# openadsb_rev_a.net
KiCad netlist of a schematic drawn in Altium Designer
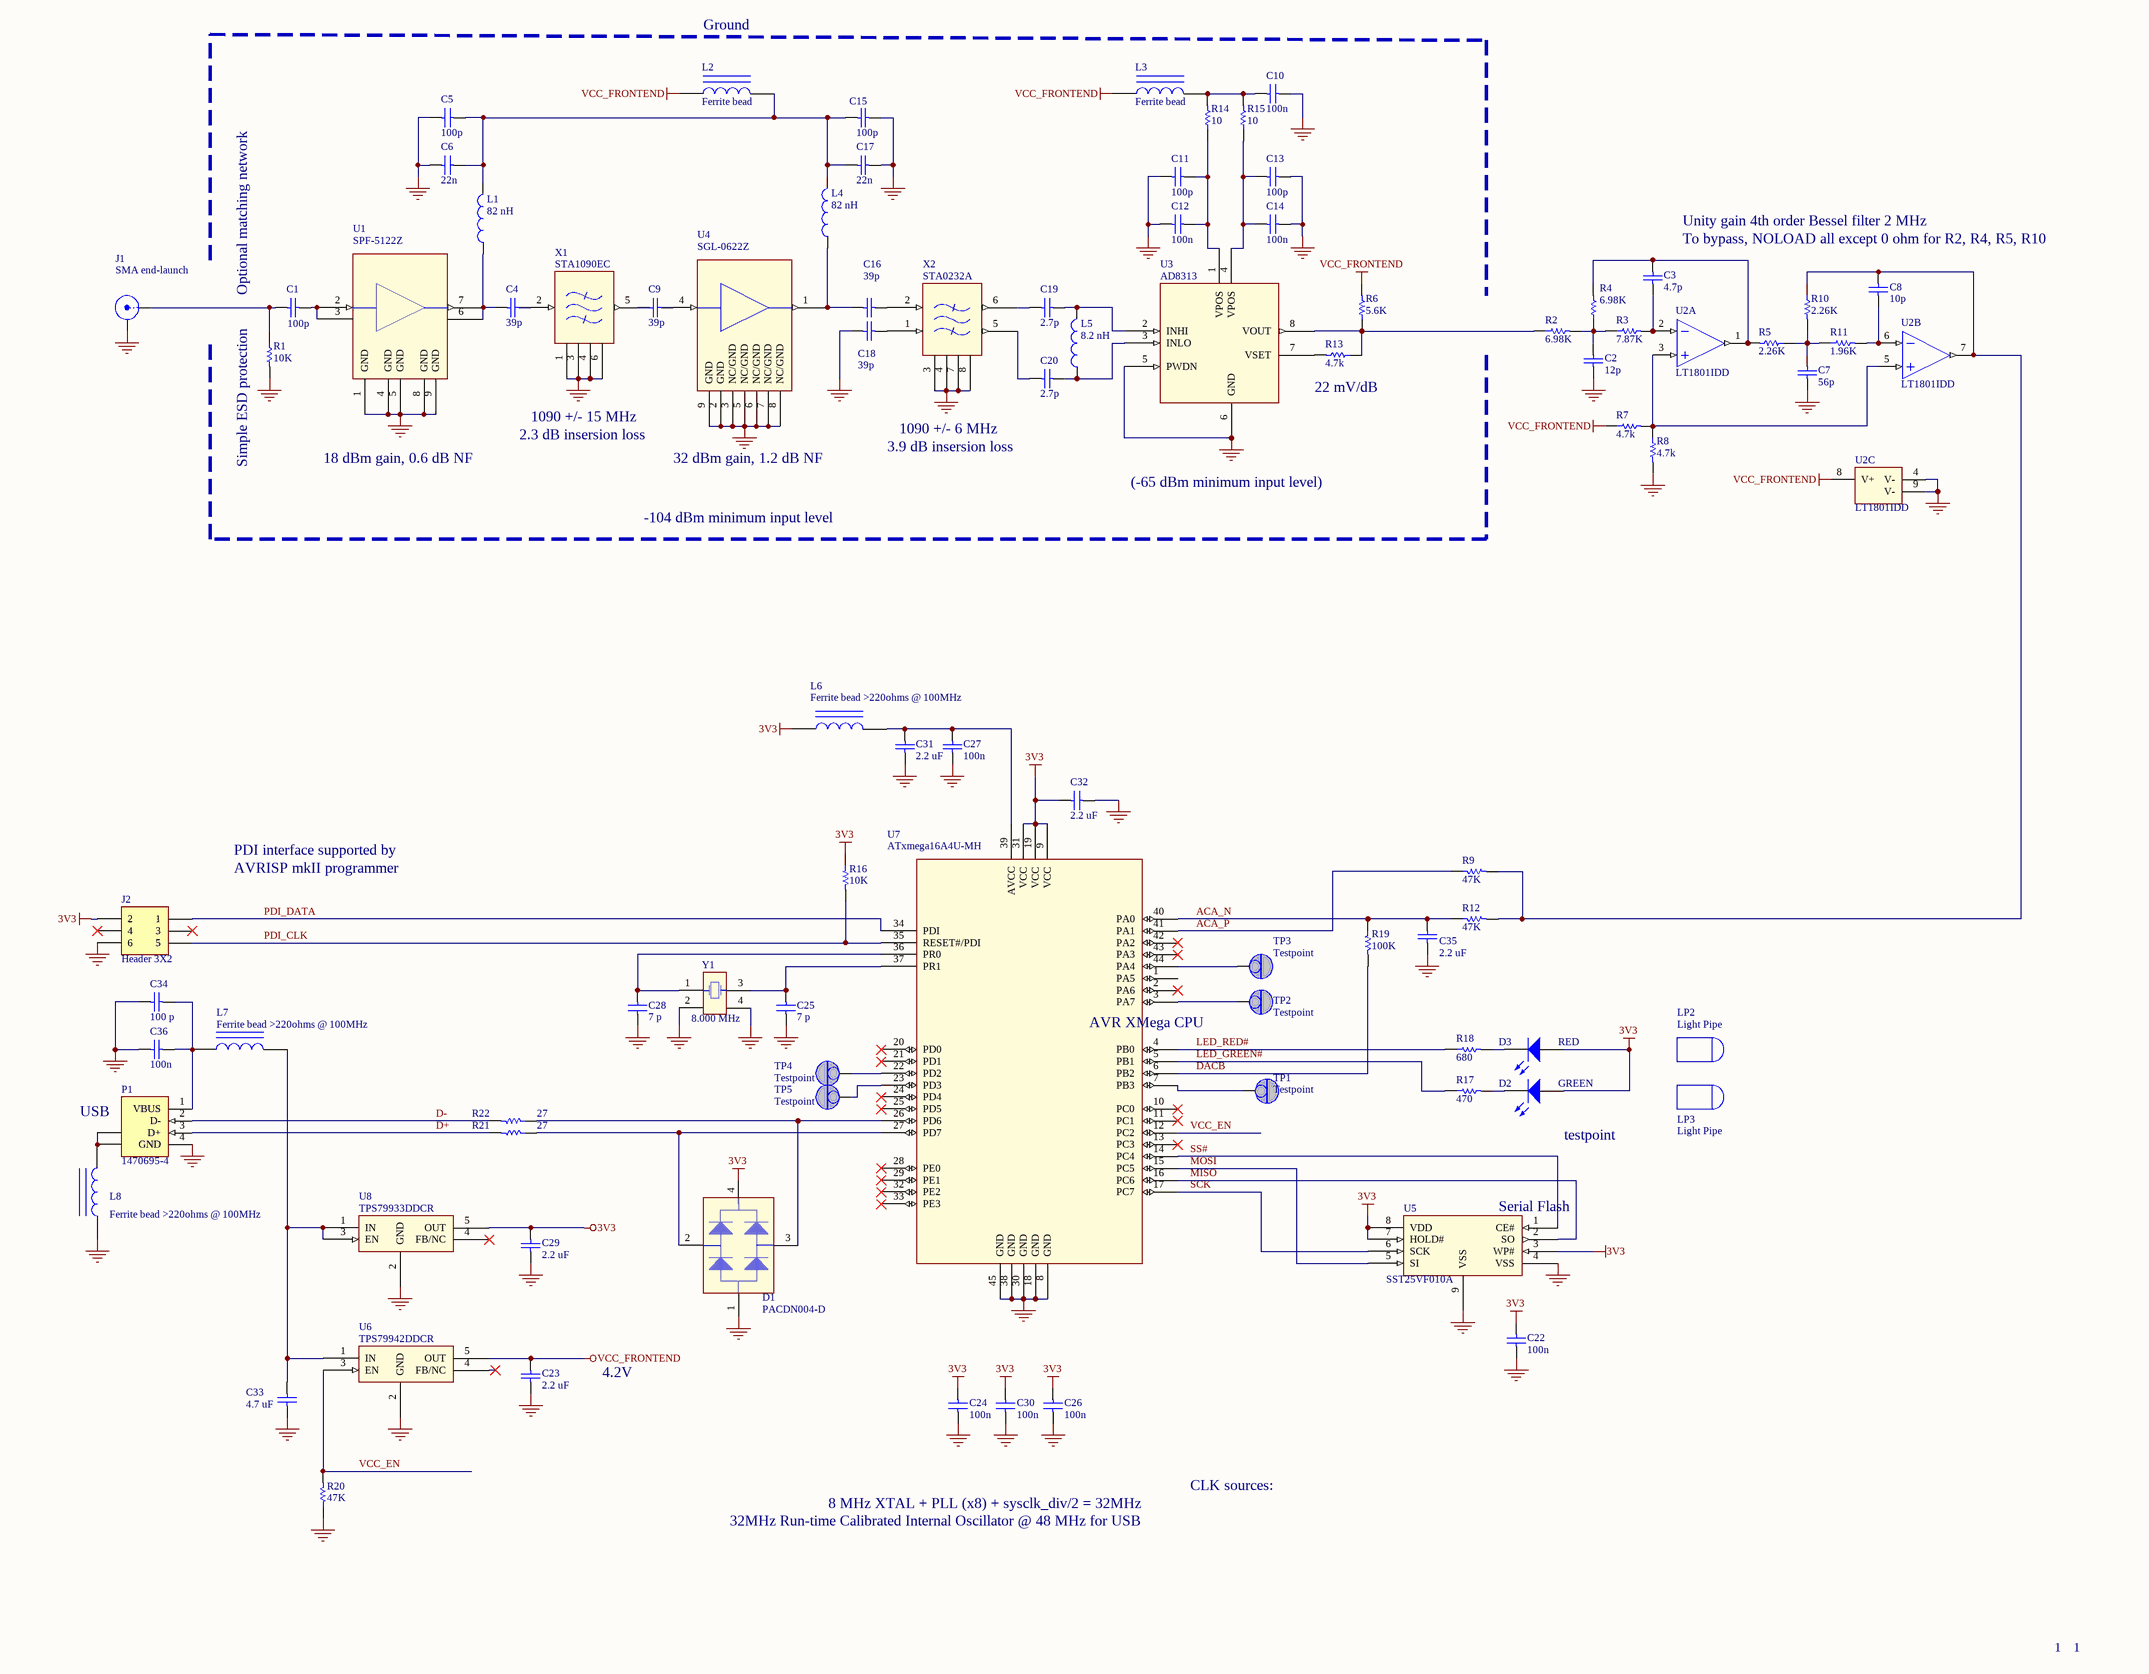
[diagram p0: openadsb_rev_a.SchDoc]

(export (version "E")
  (design (tool "Eeschema 10.0.6"))
  (components
    (comp (ref "C1")
      (value "100p")
      (description "Capacitor")
      (fields (field (name "PUBLISHER") "Altium Limited"))
      (libsource (lib "Miscellaneous Devices") (part "Cap"))
    )
    (comp (ref "C2")
      (value "12p")
      (footprint "0402")
      (description "Capacitor")
      (fields (field (name "PUBLISHER") "Altium Limited"))
      (libsource (lib "Miscellaneous Devices") (part "Cap"))
    )
    (comp (ref "C3")
      (value "4.7p")
      (footprint "0402")
      (description "Capacitor")
      (fields (field (name "PUBLISHER") "Altium Limited"))
      (libsource (lib "Miscellaneous Devices") (part "Cap"))
    )
    (comp (ref "C4")
      (value "39p")
      (description "Capacitor")
      (fields (field (name "PUBLISHER") "Altium Limited"))
      (libsource (lib "Miscellaneous Devices") (part "Cap"))
    )
    (comp (ref "C5")
      (value "100p")
      (footprint "0402")
      (description "Capacitor")
      (fields (field (name "PUBLISHER") "Altium Limited"))
      (libsource (lib "Miscellaneous Devices") (part "Cap"))
    )
    (comp (ref "C6")
      (value "22n")
      (footprint "0402")
      (description "Capacitor")
      (fields (field (name "PUBLISHER") "Altium Limited"))
      (libsource (lib "Miscellaneous Devices") (part "Cap"))
    )
    (comp (ref "C7")
      (value "56p")
      (description "Capacitor")
      (fields (field (name "PUBLISHER") "Altium Limited"))
      (libsource (lib "Miscellaneous Devices") (part "Cap"))
    )
    (comp (ref "C8")
      (value "10p")
      (footprint "0402")
      (description "Capacitor")
      (fields (field (name "PUBLISHER") "Altium Limited"))
      (libsource (lib "Miscellaneous Devices") (part "Cap"))
    )
    (comp (ref "C9")
      (value "39p")
      (description "Capacitor")
      (fields (field (name "PUBLISHER") "Altium Limited"))
      (libsource (lib "Miscellaneous Devices") (part "Cap"))
    )
    (comp (ref "C10")
      (value "100n")
      (footprint "0402")
      (description "Capacitor")
      (fields (field (name "PUBLISHER") "Altium Limited"))
      (libsource (lib "Miscellaneous Devices") (part "Cap"))
    )
    (comp (ref "C11")
      (value "100p")
      (footprint "0402")
      (description "Capacitor")
      (fields (field (name "PUBLISHER") "Altium Limited"))
      (libsource (lib "Miscellaneous Devices") (part "Cap"))
    )
    (comp (ref "C12")
      (value "100n")
      (footprint "0402")
      (description "Capacitor")
      (fields (field (name "PUBLISHER") "Altium Limited"))
      (libsource (lib "Miscellaneous Devices") (part "Cap"))
    )
    (comp (ref "C13")
      (value "100p")
      (footprint "0402")
      (description "Capacitor")
      (fields (field (name "PUBLISHER") "Altium Limited"))
      (libsource (lib "Miscellaneous Devices") (part "Cap"))
    )
    (comp (ref "C14")
      (value "100n")
      (footprint "0402")
      (description "Capacitor")
      (fields (field (name "PUBLISHER") "Altium Limited"))
      (libsource (lib "Miscellaneous Devices") (part "Cap"))
    )
    (comp (ref "C15")
      (value "100p")
      (description "Capacitor")
      (fields (field (name "PUBLISHER") "Altium Limited"))
      (libsource (lib "Miscellaneous Devices") (part "Cap"))
    )
    (comp (ref "C16")
      (value "39p")
      (description "Capacitor")
      (fields (field (name "PUBLISHER") "Altium Limited"))
      (libsource (lib "Miscellaneous Devices") (part "Cap"))
    )
    (comp (ref "C17")
      (value "22n")
      (footprint "0402")
      (description "Capacitor")
      (fields (field (name "PUBLISHER") "Altium Limited"))
      (libsource (lib "Miscellaneous Devices") (part "Cap"))
    )
    (comp (ref "C18")
      (value "39p")
      (description "Capacitor")
      (fields (field (name "PUBLISHER") "Altium Limited"))
      (libsource (lib "Miscellaneous Devices") (part "Cap"))
    )
    (comp (ref "C19")
      (value "2.7p")
      (footprint "0402")
      (description "Capacitor")
      (fields (field (name "PUBLISHER") "Altium Limited"))
      (libsource (lib "Miscellaneous Devices") (part "Cap"))
    )
    (comp (ref "C20")
      (value "2.7p")
      (footprint "0402")
      (description "Capacitor")
      (fields (field (name "PUBLISHER") "Altium Limited"))
      (libsource (lib "Miscellaneous Devices") (part "Cap"))
    )
    (comp (ref "C22")
      (value "100n")
      (footprint "0402")
      (description "Capacitor")
      (fields (field (name "PUBLISHER") "Altium Limited"))
      (libsource (lib "Miscellaneous Devices") (part "Cap"))
    )
    (comp (ref "C23")
      (value "2.2 uF")
      (footprint "1608[0603]")
      (description "Capacitor")
      (fields (field (name "PUBLISHER") "Altium Limited"))
      (libsource (lib "Miscellaneous Devices") (part "Cap"))
    )
    (comp (ref "C24")
      (value "100n")
      (footprint "0402")
      (description "Capacitor")
      (fields (field (name "PUBLISHER") "Altium Limited"))
      (libsource (lib "Miscellaneous Devices") (part "Cap"))
    )
    (comp (ref "C25")
      (value "7 p")
      (description "Capacitor")
      (fields (field (name "PUBLISHER") "Altium Limited"))
      (libsource (lib "Miscellaneous Devices") (part "Cap"))
    )
    (comp (ref "C26")
      (value "100n")
      (footprint "0402")
      (description "Capacitor")
      (fields (field (name "PUBLISHER") "Altium Limited"))
      (libsource (lib "Miscellaneous Devices") (part "Cap"))
    )
    (comp (ref "C27")
      (value "100n")
      (footprint "0402")
      (description "Capacitor")
      (fields (field (name "PUBLISHER") "Altium Limited"))
      (libsource (lib "Miscellaneous Devices") (part "Cap"))
    )
    (comp (ref "C28")
      (value "7 p")
      (description "Capacitor")
      (fields (field (name "PUBLISHER") "Altium Limited"))
      (libsource (lib "Miscellaneous Devices") (part "Cap"))
    )
    (comp (ref "C29")
      (value "2.2 uF")
      (footprint "1608[0603]")
      (description "Capacitor")
      (fields (field (name "PUBLISHER") "Altium Limited"))
      (libsource (lib "Miscellaneous Devices") (part "Cap"))
    )
    (comp (ref "C30")
      (value "100n")
      (footprint "0402")
      (description "Capacitor")
      (fields (field (name "PUBLISHER") "Altium Limited"))
      (libsource (lib "Miscellaneous Devices") (part "Cap"))
    )
    (comp (ref "C31")
      (value "2.2 uF")
      (description "Capacitor")
      (fields (field (name "PUBLISHER") "Altium Limited"))
      (libsource (lib "Miscellaneous Devices") (part "Cap"))
    )
    (comp (ref "C32")
      (value "2.2 uF")
      (footprint "1608[0603]")
      (description "Capacitor")
      (fields (field (name "PUBLISHER") "Altium Limited"))
      (libsource (lib "Miscellaneous Devices") (part "Cap"))
    )
    (comp (ref "C33")
      (value "4.7 uF")
      (description "Capacitor")
      (fields (field (name "PUBLISHER") "Altium Limited"))
      (libsource (lib "Miscellaneous Devices") (part "Cap"))
    )
    (comp (ref "C34")
      (value "100 p")
      (footprint "0402")
      (description "Capacitor")
      (fields (field (name "PUBLISHER") "Altium Limited"))
      (libsource (lib "Miscellaneous Devices") (part "Cap"))
    )
    (comp (ref "C35")
      (value "2.2 uF")
      (description "Capacitor")
      (fields (field (name "PUBLISHER") "Altium Limited"))
      (libsource (lib "Miscellaneous Devices") (part "Cap"))
    )
    (comp (ref "C36")
      (value "100n")
      (footprint "0402")
      (description "Capacitor")
      (fields (field (name "PUBLISHER") "Altium Limited"))
      (libsource (lib "Miscellaneous Devices") (part "Cap"))
    )
    (comp (ref "D1")
      (value "PACDN004-D")
      (footprint "SOT-143-RC4_L")
      (description "ESD protection")
      (fields (field (name "MANUFACTURER") "On Semi"))
      (libsource (lib "Schlib1") (part "PACDN004"))
    )
    (comp (ref "D2")
      (value "GREEN")
      (footprint "LED0603")
      (description "Typical BLUE SiC LED")
      (fields (field (name "PUBLISHER") "Altium Limited"))
      (libsource (lib "Miscellaneous Devices") (part "LED3"))
    )
    (comp (ref "D3")
      (value "RED")
      (footprint "LED0603")
      (description "Typical BLUE SiC LED")
      (fields (field (name "PUBLISHER") "Altium Limited"))
      (libsource (lib "Miscellaneous Devices") (part "LED3"))
    )
    (comp (ref "J1")
      (value "SMA end-launch")
      (footprint "SMA_ENDLAUNCH")
      (description "SMB Straight Connector")
      (fields (field (name "PUBLISHER") "Altium Limited"))
      (libsource (lib "Miscellaneous Connectors") (part "SMB"))
    )
    (comp (ref "J2")
      (value "Header 3X2")
      (footprint "HDR2X3")
      (description "Header, 3-Pin, Dual row")
      (fields (field (name "PUBLISHER") "Altium Limited"))
      (libsource (lib "Miscellaneous Connectors") (part "Header 3X2"))
    )
    (comp (ref "L1")
      (value "82 nH")
      (footprint "0402")
      (description "Inductor")
      (fields
        (field (name "PARTNUMBER") "TKS2388CT")
        (field (name "MANUFACTURER") "TOKO")
        (field (name "PUBLISHER") "Altium Limited")
      )
      (libsource (lib "Miscellaneous Devices") (part "Inductor"))
    )
    (comp (ref "L2")
      (value "Ferrite bead")
      (footprint "0402")
      (description "Magnetic-Core Inductor")
      (fields (field (name "PUBLISHER") "Altium Limited"))
      (libsource (lib "") (part "Inductor Iron_1"))
    )
    (comp (ref "L3")
      (value "Ferrite bead")
      (footprint "0402")
      (description "Magnetic-Core Inductor")
      (fields (field (name "PUBLISHER") "Altium Limited"))
      (libsource (lib "") (part "Inductor Iron_1"))
    )
    (comp (ref "L4")
      (value "82 nH")
      (footprint "0402")
      (description "Inductor")
      (fields (field (name "PUBLISHER") "Altium Limited"))
      (libsource (lib "Miscellaneous Devices") (part "Inductor"))
    )
    (comp (ref "L5")
      (value "8.2 nH")
      (footprint "0402")
      (description "Inductor")
      (fields (field (name "PUBLISHER") "Altium Limited"))
      (libsource (lib "Miscellaneous Devices") (part "Inductor"))
    )
    (comp (ref "L6")
      (value "Ferrite bead >220ohms @ 100MHz")
      (footprint "0402")
      (description "Magnetic-Core Inductor")
      (fields (field (name "PUBLISHER") "Altium Limited"))
      (libsource (lib "Miscellaneous Devices") (part "Inductor Iron"))
    )
    (comp (ref "L7")
      (value "Ferrite bead >220ohms @ 100MHz")
      (footprint "0402")
      (description "Magnetic-Core Inductor")
      (fields (field (name "PUBLISHER") "Altium Limited"))
      (libsource (lib "Miscellaneous Devices") (part "Inductor Iron"))
    )
    (comp (ref "L8")
      (value "Ferrite bead >220ohms @ 100MHz")
      (footprint "0402")
      (description "Magnetic-Core Inductor")
      (fields (field (name "PUBLISHER") "Altium Limited"))
      (libsource (lib "Miscellaneous Devices") (part "Inductor Iron"))
    )
    (comp (ref "LP2")
      (value "Light Pipe")
      (footprint "LIGHTPIPE")
      (description "light pipe")
      (fields (field (name "PARTNUMBER") "PLP2-215") (field (name "MANUFACTURER") "Bivar"))
      (libsource (lib "Schlib1") (part "LIGHT_PIPE"))
    )
    (comp (ref "LP3")
      (value "Light Pipe")
      (description "light pipe")
      (fields (field (name "PARTNUMBER") "PLP2-215") (field (name "MANUFACTURER") "Bivar"))
      (libsource (lib "Schlib1") (part "LIGHT_PIPE"))
    )
    (comp (ref "P1")
      (value "1470695-4")
      (footprint "1470695A")
      (description "USB 1.1, Right Angle, SMT, A Type, Plug, 4 Position, Black")
      (fields (field (name "PUBLISHER") "Altium Limited"))
      (libsource (lib "AMP Serial Bus USB") (part "1470695-4"))
    )
    (comp (ref "R1")
      (value "10K")
      (footprint "0402")
      (description "Resistor")
      (fields (field (name "PUBLISHER") "Altium Limited"))
      (libsource (lib "Miscellaneous Devices") (part "Res1"))
    )
    (comp (ref "R2")
      (value "6.98K")
      (footprint "0402")
      (description "Resistor")
      (fields (field (name "PUBLISHER") "Altium Limited"))
      (libsource (lib "Miscellaneous Devices") (part "Res1"))
    )
    (comp (ref "R3")
      (value "7.87K")
      (footprint "0402")
      (description "Resistor")
      (fields (field (name "PUBLISHER") "Altium Limited"))
      (libsource (lib "Miscellaneous Devices") (part "Res1"))
    )
    (comp (ref "R4")
      (value "6.98K")
      (footprint "0402")
      (description "Resistor")
      (fields (field (name "PUBLISHER") "Altium Limited"))
      (libsource (lib "Miscellaneous Devices") (part "Res1"))
    )
    (comp (ref "R5")
      (value "2.26K")
      (footprint "0402")
      (description "Resistor")
      (fields (field (name "PUBLISHER") "Altium Limited"))
      (libsource (lib "Miscellaneous Devices") (part "Res1"))
    )
    (comp (ref "R6")
      (value "5.6K")
      (footprint "0402")
      (description "Resistor")
      (fields (field (name "PUBLISHER") "Altium Limited"))
      (libsource (lib "Miscellaneous Devices") (part "Res1"))
    )
    (comp (ref "R7")
      (value "4.7k")
      (footprint "0402")
      (description "Resistor")
      (fields (field (name "PUBLISHER") "Altium Limited"))
      (libsource (lib "Miscellaneous Devices") (part "Res1"))
    )
    (comp (ref "R8")
      (value "4.7k")
      (footprint "0402")
      (description "Resistor")
      (fields (field (name "PUBLISHER") "Altium Limited"))
      (libsource (lib "Miscellaneous Devices") (part "Res1"))
    )
    (comp (ref "R9")
      (value "47K")
      (footprint "0402")
      (description "Resistor")
      (fields (field (name "PUBLISHER") "Altium Limited"))
      (libsource (lib "Miscellaneous Devices") (part "Res1"))
    )
    (comp (ref "R10")
      (value "2.26K")
      (footprint "0402")
      (description "Resistor")
      (fields (field (name "PUBLISHER") "Altium Limited"))
      (libsource (lib "Miscellaneous Devices") (part "Res1"))
    )
    (comp (ref "R11")
      (value "1.96K")
      (footprint "0402")
      (description "Resistor")
      (fields (field (name "PUBLISHER") "Altium Limited"))
      (libsource (lib "Miscellaneous Devices") (part "Res1"))
    )
    (comp (ref "R12")
      (value "47K")
      (footprint "0402")
      (description "Resistor")
      (fields (field (name "PUBLISHER") "Altium Limited"))
      (libsource (lib "Miscellaneous Devices") (part "Res1"))
    )
    (comp (ref "R13")
      (value "4.7k")
      (footprint "0402")
      (description "Resistor")
      (fields (field (name "PUBLISHER") "Altium Limited"))
      (libsource (lib "Miscellaneous Devices") (part "Res1"))
    )
    (comp (ref "R14")
      (value "10")
      (footprint "0402")
      (description "Resistor")
      (fields (field (name "PUBLISHER") "Altium Limited"))
      (libsource (lib "Miscellaneous Devices") (part "Res1"))
    )
    (comp (ref "R15")
      (value "10")
      (footprint "0402")
      (description "Resistor")
      (fields (field (name "PUBLISHER") "Altium Limited"))
      (libsource (lib "Miscellaneous Devices") (part "Res1"))
    )
    (comp (ref "R16")
      (value "10K")
      (footprint "0402")
      (description "Resistor")
      (fields (field (name "PUBLISHER") "Altium Limited"))
      (libsource (lib "Miscellaneous Devices") (part "Res1"))
    )
    (comp (ref "R17")
      (value "470")
      (footprint "0402")
      (description "Resistor")
      (fields (field (name "PUBLISHER") "Altium Limited"))
      (libsource (lib "Miscellaneous Devices") (part "Res1"))
    )
    (comp (ref "R18")
      (value "680")
      (footprint "0402")
      (description "Resistor")
      (fields (field (name "PUBLISHER") "Altium Limited"))
      (libsource (lib "Miscellaneous Devices") (part "Res1"))
    )
    (comp (ref "R19")
      (value "100K")
      (footprint "0402")
      (description "Resistor")
      (fields (field (name "PUBLISHER") "Altium Limited"))
      (libsource (lib "Miscellaneous Devices") (part "Res1"))
    )
    (comp (ref "R20")
      (value "47K")
      (footprint "0402")
      (description "Resistor")
      (fields (field (name "PUBLISHER") "Altium Limited"))
      (libsource (lib "Miscellaneous Devices") (part "Res1"))
    )
    (comp (ref "R21")
      (value "27")
      (footprint "0402")
      (description "Resistor")
      (fields (field (name "PUBLISHER") "Altium Limited"))
      (libsource (lib "Miscellaneous Devices") (part "Res1"))
    )
    (comp (ref "R22")
      (value "27")
      (footprint "0402")
      (description "Resistor")
      (fields (field (name "PUBLISHER") "Altium Limited"))
      (libsource (lib "Miscellaneous Devices") (part "Res1"))
    )
    (comp (ref "TP1")
      (value "Testpoint")
      (footprint "Testpoint_via")
      (libsource (lib "") (part "Testpoint_1"))
    )
    (comp (ref "TP2")
      (value "Testpoint")
      (footprint "Testpoint_via")
      (libsource (lib "") (part "Testpoint_1"))
    )
    (comp (ref "TP3")
      (value "Testpoint")
      (footprint "Testpoint_via")
      (libsource (lib "") (part "Testpoint_1"))
    )
    (comp (ref "TP4")
      (value "Testpoint")
      (footprint "Testpoint_via")
      (libsource (lib "adsb_usb") (part "Testpoint"))
    )
    (comp (ref "TP5")
      (value "Testpoint")
      (footprint "Testpoint_via")
      (libsource (lib "adsb_usb") (part "Testpoint"))
    )
    (comp (ref "U1")
      (value "SPF-5122Z")
      (footprint "DFN8_2x2mm")
      (fields (field (name "MANUFACTURER") "Sirenza"))
      (libsource (lib "Schlib1") (part "LNA1"))
    )
    (comp (ref "U2")
      (value "LT1801IDD")
      (footprint "DFN8_3x3mm")
      (fields (field (name "MANUFACTURER") "Linear Tech"))
      (libsource (lib "") (part "LT1801_1"))
    )
    (comp (ref "U3")
      (value "AD8313")
      (footprint "MSOP-MS8_N")
      (description "AD8313 Logarithmic Amp")
      (libsource (lib "Schlib1") (part "AD8313"))
    )
    (comp (ref "U4")
      (value "SGL-0622Z")
      (footprint "DFN8_2x2mm")
      (fields (field (name "MANUFACTURER") "RFMD"))
      (libsource (lib "adsb_usb") (part "SGL0622Z"))
    )
    (comp (ref "U5")
      (value "SST25VF010A")
      (footprint "WSON-8")
      (fields (field (name "MANUFACTURER") "SST"))
      (libsource (lib "Schlib1") (part "SERFLASH"))
    )
    (comp (ref "U6")
      (value "TPS79942DDCR")
      (footprint "SOT23-5AN")
      (fields (field (name "MANUFACTURER") "Texas Instruments"))
      (libsource (lib "Schlib1") (part "TPS799XX"))
    )
    (comp (ref "U7")
      (value "ATxmega16A4U-MH")
      (footprint "QFN50P700X700-44W3N")
      (fields (field (name "MANUFACTURER") "Atmel"))
      (libsource (lib "adsb_usb") (part "ATXMEGA164AU"))
    )
    (comp (ref "U8")
      (value "TPS79933DDCR")
      (footprint "SOT23-5AN")
      (fields (field (name "MANUFACTURER") "Texas Instruments"))
      (libsource (lib "Schlib1") (part "TPS799XX"))
    )
    (comp (ref "X1")
      (value "STA1090EC")
      (footprint "STA1090EC")
      (libsource (lib "Schlib1") (part "BP_FILTER_UNBAL"))
    )
    (comp (ref "X2") (value "STA0232A") (libsource (lib "Schlib1") (part "BP_FILTER_BAL2")))
    (comp (ref "Y1")
      (value "8.000 MHz")
      (footprint "ABM3C")
      (fields (field (name "MANUFACTURER") "Abracon") (field (name "PARTNUMBER") "ABM3B-8.000MHZ-B2-T"))
      (libsource (lib "Schlib1") (part "XTAL_4"))
    )
  )
  (nets
    (net (code "1") (name "/ACA_N") (class "Default")
      (node (ref "C35") (pin "1") (pinfunction "1_1") (pintype "passive"))
      (node (ref "R12") (pin "1") (pinfunction "1_1") (pintype "passive"))
      (node (ref "R19") (pin "1") (pinfunction "1_1") (pintype "passive"))
      (node (ref "U7") (pin "40") (pinfunction "PA0_40") (pintype "bidirectional"))
    )
    (net (code "2") (name "/ACA_P") (class "Default")
      (node (ref "R9") (pin "1") (pinfunction "1_1") (pintype "passive"))
      (node (ref "U7") (pin "41") (pinfunction "PA1_41") (pintype "bidirectional"))
    )
    (net (code "3") (name "/D+") (class "Default")
      (node (ref "P1") (pin "3") (pinfunction "D+_3") (pintype "input"))
      (node (ref "R21") (pin "2") (pinfunction "2_2") (pintype "passive"))
    )
    (net (code "4") (name "/D-") (class "Default")
      (node (ref "P1") (pin "2") (pinfunction "D-_2") (pintype "input"))
      (node (ref "R22") (pin "2") (pinfunction "2_2") (pintype "passive"))
    )
    (net (code "5") (name "/DACB") (class "Default")
      (node (ref "R19") (pin "2") (pinfunction "2_2") (pintype "passive"))
      (node (ref "U7") (pin "6") (pinfunction "PB2_6") (pintype "bidirectional"))
    )
    (net (code "6") (name "/LED_GREEN#") (class "Default")
      (node (ref "R17") (pin "1") (pinfunction "1_1") (pintype "passive"))
      (node (ref "U7") (pin "5") (pinfunction "PB1_5") (pintype "bidirectional"))
    )
    (net (code "7") (name "/LED_RED#") (class "Default")
      (node (ref "R18") (pin "1") (pinfunction "1_1") (pintype "passive"))
      (node (ref "U7") (pin "4") (pinfunction "PB0_4") (pintype "bidirectional"))
    )
    (net (code "8") (name "/MISO") (class "Default")
      (node (ref "U5") (pin "2") (pinfunction "SO_2") (pintype "output"))
      (node (ref "U7") (pin "16") (pinfunction "PC6_16") (pintype "bidirectional"))
    )
    (net (code "9") (name "/MOSI") (class "Default")
      (node (ref "U5") (pin "5") (pinfunction "SI_5") (pintype "input"))
      (node (ref "U7") (pin "15") (pinfunction "PC5_15") (pintype "bidirectional"))
    )
    (net (code "10") (name "/PDI_CLK") (class "Default")
      (node (ref "J2") (pin "5") (pinfunction "5_5") (pintype "passive"))
      (node (ref "R16") (pin "2") (pinfunction "2_2") (pintype "passive"))
      (node (ref "U7") (pin "35") (pinfunction "RESET#/PDI_35") (pintype "passive"))
    )
    (net (code "11") (name "/PDI_DATA") (class "Default")
      (node (ref "J2") (pin "1") (pinfunction "1_1") (pintype "passive"))
      (node (ref "U7") (pin "34") (pinfunction "PDI_34") (pintype "passive"))
    )
    (net (code "12") (name "/SCK") (class "Default")
      (node (ref "U5") (pin "6") (pinfunction "SCK_6") (pintype "input"))
      (node (ref "U7") (pin "17") (pinfunction "PC7_17") (pintype "bidirectional"))
    )
    (net (code "13") (name "/SS#") (class "Default")
      (node (ref "U5") (pin "1") (pinfunction "CE#_1") (pintype "input"))
      (node (ref "U7") (pin "14") (pinfunction "PC4_14") (pintype "bidirectional"))
    )
    (net (code "14") (name "/VCC_EN") (class "Default")
      (node (ref "R20") (pin "2") (pinfunction "2_2") (pintype "passive"))
      (node (ref "U6") (pin "3") (pinfunction "EN_3") (pintype "input"))
      (node (ref "U7") (pin "12") (pinfunction "PC2_12") (pintype "bidirectional"))
    )
    (net (code "15") (name "3V3") (class "Default")
      (node (ref "C22") (pin "1") (pinfunction "1_1") (pintype "passive"))
      (node (ref "C24") (pin "1") (pinfunction "1_1") (pintype "passive"))
      (node (ref "C26") (pin "1") (pinfunction "1_1") (pintype "passive"))
      (node (ref "C29") (pin "1") (pinfunction "1_1") (pintype "passive"))
      (node (ref "C30") (pin "1") (pinfunction "1_1") (pintype "passive"))
      (node (ref "C32") (pin "1") (pinfunction "1_1") (pintype "passive"))
      (node (ref "D1") (pin "4") (pinfunction "V_4") (pintype "passive"))
      (node (ref "D2") (pin "A") (pinfunction "A_A") (pintype "passive"))
      (node (ref "D3") (pin "A") (pinfunction "A_A") (pintype "passive"))
      (node (ref "J2") (pin "2") (pinfunction "2_2") (pintype "passive"))
      (node (ref "L6") (pin "2") (pinfunction "2_2") (pintype "passive"))
      (node (ref "R16") (pin "1") (pinfunction "1_1") (pintype "passive"))
      (node (ref "U5") (pin "3") (pinfunction "WP#_3") (pintype "input"))
      (node (ref "U5") (pin "7") (pinfunction "HOLD#_7") (pintype "input"))
      (node (ref "U5") (pin "8") (pinfunction "VDD_8") (pintype "power_in"))
      (node (ref "U7") (pin "19") (pinfunction "VCC_19") (pintype "power_in"))
      (node (ref "U7") (pin "31") (pinfunction "VCC_31") (pintype "power_in"))
      (node (ref "U7") (pin "9") (pinfunction "VCC_9") (pintype "power_in"))
      (node (ref "U8") (pin "5") (pinfunction "OUT_5") (pintype "power_in"))
    )
    (net (code "16") (name "GND") (class "Default")
      (node (ref "C10") (pin "2") (pinfunction "2_2") (pintype "passive"))
      (node (ref "C11") (pin "2") (pinfunction "2_2") (pintype "passive"))
      (node (ref "C12") (pin "2") (pinfunction "2_2") (pintype "passive"))
      (node (ref "C13") (pin "1") (pinfunction "1_1") (pintype "passive"))
      (node (ref "C14") (pin "1") (pinfunction "1_1") (pintype "passive"))
      (node (ref "C15") (pin "2") (pinfunction "2_2") (pintype "passive"))
      (node (ref "C17") (pin "2") (pinfunction "2_2") (pintype "passive"))
      (node (ref "C18") (pin "1") (pinfunction "1_1") (pintype "passive"))
      (node (ref "C2") (pin "1") (pinfunction "1_1") (pintype "passive"))
      (node (ref "C22") (pin "2") (pinfunction "2_2") (pintype "passive"))
      (node (ref "C23") (pin "2") (pinfunction "2_2") (pintype "passive"))
      (node (ref "C24") (pin "2") (pinfunction "2_2") (pintype "passive"))
      (node (ref "C25") (pin "1") (pinfunction "1_1") (pintype "passive"))
      (node (ref "C26") (pin "2") (pinfunction "2_2") (pintype "passive"))
      (node (ref "C27") (pin "2") (pinfunction "2_2") (pintype "passive"))
      (node (ref "C28") (pin "1") (pinfunction "1_1") (pintype "passive"))
      (node (ref "C29") (pin "2") (pinfunction "2_2") (pintype "passive"))
      (node (ref "C30") (pin "2") (pinfunction "2_2") (pintype "passive"))
      (node (ref "C31") (pin "2") (pinfunction "2_2") (pintype "passive"))
      (node (ref "C32") (pin "2") (pinfunction "2_2") (pintype "passive"))
      (node (ref "C33") (pin "2") (pinfunction "2_2") (pintype "passive"))
      (node (ref "C34") (pin "2") (pinfunction "2_2") (pintype "passive"))
      (node (ref "C35") (pin "2") (pinfunction "2_2") (pintype "passive"))
      (node (ref "C36") (pin "2") (pinfunction "2_2") (pintype "passive"))
      (node (ref "C5") (pin "2") (pinfunction "2_2") (pintype "passive"))
      (node (ref "C6") (pin "2") (pinfunction "2_2") (pintype "passive"))
      (node (ref "C7") (pin "1") (pinfunction "1_1") (pintype "passive"))
      (node (ref "D1") (pin "1") (pinfunction "GND_1") (pintype "passive"))
      (node (ref "J1") (pin "2") (pinfunction "Y_2") (pintype "passive"))
      (node (ref "J2") (pin "6") (pinfunction "6_6") (pintype "passive"))
      (node (ref "L8") (pin "2") (pinfunction "2_2") (pintype "passive"))
      (node (ref "P1") (pin "4") (pinfunction "GND_4") (pintype "power_in"))
      (node (ref "R1") (pin "2") (pinfunction "2_2") (pintype "passive"))
      (node (ref "R20") (pin "1") (pinfunction "1_1") (pintype "passive"))
      (node (ref "R8") (pin "2") (pinfunction "2_2") (pintype "passive"))
      (node (ref "U1") (pin "1") (pinfunction "GND_1") (pintype "power_in"))
      (node (ref "U1") (pin "4") (pinfunction "GND_4") (pintype "power_in"))
      (node (ref "U1") (pin "5") (pinfunction "GND_5") (pintype "power_in"))
      (node (ref "U1") (pin "8") (pinfunction "GND_8") (pintype "power_in"))
      (node (ref "U1") (pin "9") (pinfunction "GND_9") (pintype "power_in"))
      (node (ref "U2") (pin "4") (pinfunction "V-_4") (pintype "power_in"))
      (node (ref "U2") (pin "9") (pinfunction "V-_9") (pintype "power_in"))
      (node (ref "U3") (pin "5") (pinfunction "PWDN_5") (pintype "input"))
      (node (ref "U3") (pin "6") (pinfunction "GND_6") (pintype "power_in"))
      (node (ref "U4") (pin "2") (pinfunction "GND_2") (pintype "passive"))
      (node (ref "U4") (pin "3") (pinfunction "NC/GND_3") (pintype "passive"))
      (node (ref "U4") (pin "5") (pinfunction "NC/GND_5") (pintype "passive"))
      (node (ref "U4") (pin "6") (pinfunction "NC/GND_6") (pintype "passive"))
      (node (ref "U4") (pin "7") (pinfunction "NC/GND_7") (pintype "passive"))
      (node (ref "U4") (pin "8") (pinfunction "NC/GND_8") (pintype "passive"))
      (node (ref "U4") (pin "9") (pinfunction "GND_9") (pintype "power_in"))
      (node (ref "U5") (pin "4") (pinfunction "VSS_4") (pintype "power_in"))
      (node (ref "U5") (pin "9") (pinfunction "VSS_9") (pintype "power_in"))
      (node (ref "U6") (pin "2") (pinfunction "GND_2") (pintype "power_in"))
      (node (ref "U7") (pin "18") (pinfunction "GND_18") (pintype "power_in"))
      (node (ref "U7") (pin "30") (pinfunction "GND_30") (pintype "power_in"))
      (node (ref "U7") (pin "38") (pinfunction "GND_38") (pintype "power_in"))
      (node (ref "U7") (pin "45") (pinfunction "GND_45") (pintype "power_in"))
      (node (ref "U7") (pin "8") (pinfunction "GND_8") (pintype "power_in"))
      (node (ref "U8") (pin "2") (pinfunction "GND_2") (pintype "power_in"))
      (node (ref "X1") (pin "1") (pinfunction "GND_1") (pintype "passive"))
      (node (ref "X1") (pin "3") (pinfunction "GND_3") (pintype "passive"))
      (node (ref "X1") (pin "4") (pinfunction "GND_4") (pintype "passive"))
      (node (ref "X1") (pin "6") (pinfunction "GND_6") (pintype "passive"))
      (node (ref "X2") (pin "3") (pinfunction "GND_3") (pintype "passive"))
      (node (ref "X2") (pin "4") (pinfunction "GND_4") (pintype "passive"))
      (node (ref "X2") (pin "7") (pinfunction "GND_7") (pintype "passive"))
      (node (ref "X2") (pin "8") (pinfunction "GND_8") (pintype "passive"))
      (node (ref "Y1") (pin "2") (pinfunction "GND_2") (pintype "passive"))
      (node (ref "Y1") (pin "4") (pinfunction "OSC1_4") (pintype "passive"))
    )
    (net (code "17") (name "Net-(C2-Pad2)") (class "Default")
      (node (ref "C2") (pin "2") (pinfunction "2_2") (pintype "passive"))
      (node (ref "R2") (pin "2") (pinfunction "2_2") (pintype "passive"))
      (node (ref "R3") (pin "1") (pinfunction "1_1") (pintype "passive"))
      (node (ref "R4") (pin "1") (pinfunction "1_1") (pintype "passive"))
    )
    (net (code "18") (name "Net-(C7-Pad2)") (class "Default")
      (node (ref "C7") (pin "2") (pinfunction "2_2") (pintype "passive"))
      (node (ref "R10") (pin "2") (pinfunction "2_2") (pintype "passive"))
      (node (ref "R11") (pin "1") (pinfunction "1_1") (pintype "passive"))
      (node (ref "R5") (pin "1") (pinfunction "1_1") (pintype "passive"))
    )
    (net (code "19") (name "Net-(C10-Pad1)") (class "Default")
      (node (ref "C10") (pin "1") (pinfunction "1_1") (pintype "passive"))
      (node (ref "L3") (pin "2") (pinfunction "2_2") (pintype "passive"))
      (node (ref "R14") (pin "2") (pinfunction "2_2") (pintype "passive"))
      (node (ref "R15") (pin "2") (pinfunction "2_2") (pintype "passive"))
    )
    (net (code "20") (name "Net-(C11-Pad1)") (class "Default")
      (node (ref "C11") (pin "1") (pinfunction "1_1") (pintype "passive"))
      (node (ref "C12") (pin "1") (pinfunction "1_1") (pintype "passive"))
      (node (ref "R14") (pin "1") (pinfunction "1_1") (pintype "passive"))
      (node (ref "U3") (pin "1") (pinfunction "VPOS_1") (pintype "power_in"))
    )
    (net (code "21") (name "Net-(C13-Pad2)") (class "Default")
      (node (ref "C13") (pin "2") (pinfunction "2_2") (pintype "passive"))
      (node (ref "C14") (pin "2") (pinfunction "2_2") (pintype "passive"))
      (node (ref "R15") (pin "1") (pinfunction "1_1") (pintype "passive"))
      (node (ref "U3") (pin "4") (pinfunction "VPOS_4") (pintype "power_in"))
    )
    (net (code "22") (name "Net-(C15-Pad1)") (class "Default")
      (node (ref "C15") (pin "1") (pinfunction "1_1") (pintype "passive"))
      (node (ref "C17") (pin "1") (pinfunction "1_1") (pintype "passive"))
      (node (ref "C5") (pin "1") (pinfunction "1_1") (pintype "passive"))
      (node (ref "C6") (pin "1") (pinfunction "1_1") (pintype "passive"))
      (node (ref "L1") (pin "2") (pinfunction "2_2") (pintype "passive"))
      (node (ref "L2") (pin "2") (pinfunction "2_2") (pintype "passive"))
      (node (ref "L4") (pin "2") (pinfunction "2_2") (pintype "passive"))
    )
    (net (code "23") (name "Net-(D2-PadK)") (class "Default")
      (node (ref "D2") (pin "K") (pinfunction "K_K") (pintype "passive"))
      (node (ref "R17") (pin "2") (pinfunction "2_2") (pintype "passive"))
    )
    (net (code "24") (name "Net-(D3-PadK)") (class "Default")
      (node (ref "D3") (pin "K") (pinfunction "K_K") (pintype "passive"))
      (node (ref "R18") (pin "2") (pinfunction "2_2") (pintype "passive"))
    )
    (net (code "25") (name "Net-(J1-X)") (class "Default")
      (node (ref "C1") (pin "1") (pinfunction "1_1") (pintype "passive"))
      (node (ref "J1") (pin "1") (pinfunction "X_1") (pintype "passive"))
      (node (ref "R1") (pin "1") (pinfunction "1_1") (pintype "passive"))
    )
    (net (code "26") (name "Net-(L8-Pad1)") (class "Default")
      (node (ref "L8") (pin "1") (pinfunction "1_1") (pintype "passive"))
      (node (ref "P1") (pin "5") (pinfunction "SHLD_5") (pintype "passive"))
      (node (ref "P1") (pin "6") (pinfunction "SHLD_6") (pintype "passive"))
    )
    (net (code "27") (name "Net-(P1-VBUS)") (class "Default")
      (node (ref "C34") (pin "1") (pinfunction "1_1") (pintype "passive"))
      (node (ref "C36") (pin "1") (pinfunction "1_1") (pintype "passive"))
      (node (ref "L7") (pin "2") (pinfunction "2_2") (pintype "passive"))
      (node (ref "P1") (pin "1") (pinfunction "VBUS_1") (pintype "power_in"))
    )
    (net (code "28") (name "Net-(U1-IN)") (class "Default")
      (node (ref "C1") (pin "2") (pinfunction "2_2") (pintype "passive"))
      (node (ref "U1") (pin "2") (pinfunction "IN_2") (pintype "input"))
      (node (ref "U1") (pin "3") (pinfunction "NC_3") (pintype "power_in"))
    )
    (net (code "29") (name "Net-(U1-OUT)") (class "Default")
      (node (ref "C4") (pin "1") (pinfunction "1_1") (pintype "passive"))
      (node (ref "L1") (pin "1") (pinfunction "1_1") (pintype "passive"))
      (node (ref "U1") (pin "6") (pinfunction "NC_6") (pintype "power_in"))
      (node (ref "U1") (pin "7") (pinfunction "OUT_7") (pintype "output"))
    )
    (net (code "30") (name "Net-(U2A-IN1+)") (class "Default")
      (node (ref "R7") (pin "2") (pinfunction "2_2") (pintype "passive"))
      (node (ref "R8") (pin "1") (pinfunction "1_1") (pintype "passive"))
      (node (ref "U2") (pin "3") (pinfunction "IN1+_3") (pintype "input"))
      (node (ref "U2") (pin "5") (pinfunction "IN2+_5") (pintype "input"))
    )
    (net (code "31") (name "Net-(U2A-IN1-)") (class "Default")
      (node (ref "C3") (pin "1") (pinfunction "1_1") (pintype "passive"))
      (node (ref "R3") (pin "2") (pinfunction "2_2") (pintype "passive"))
      (node (ref "U2") (pin "2") (pinfunction "IN1-_2") (pintype "input"))
    )
    (net (code "32") (name "Net-(U2A-OUT1)") (class "Default")
      (node (ref "C3") (pin "2") (pinfunction "2_2") (pintype "passive"))
      (node (ref "R4") (pin "2") (pinfunction "2_2") (pintype "passive"))
      (node (ref "R5") (pin "2") (pinfunction "2_2") (pintype "passive"))
      (node (ref "U2") (pin "1") (pinfunction "OUT1_1") (pintype "output"))
    )
    (net (code "33") (name "Net-(U2B-IN2-)") (class "Default")
      (node (ref "C8") (pin "1") (pinfunction "1_1") (pintype "passive"))
      (node (ref "R11") (pin "2") (pinfunction "2_2") (pintype "passive"))
      (node (ref "U2") (pin "6") (pinfunction "IN2-_6") (pintype "input"))
    )
    (net (code "34") (name "Net-(U2B-OUT2)") (class "Default")
      (node (ref "C8") (pin "2") (pinfunction "2_2") (pintype "passive"))
      (node (ref "R10") (pin "1") (pinfunction "1_1") (pintype "passive"))
      (node (ref "R12") (pin "2") (pinfunction "2_2") (pintype "passive"))
      (node (ref "R9") (pin "2") (pinfunction "2_2") (pintype "passive"))
      (node (ref "U2") (pin "7") (pinfunction "OUT2_7") (pintype "output"))
    )
    (net (code "35") (name "Net-(U3-INHI)") (class "Default")
      (node (ref "C19") (pin "2") (pinfunction "2_2") (pintype "passive"))
      (node (ref "L5") (pin "2") (pinfunction "2_2") (pintype "passive"))
      (node (ref "U3") (pin "2") (pinfunction "INHI_2") (pintype "input"))
    )
    (net (code "36") (name "Net-(U3-INLO)") (class "Default")
      (node (ref "C20") (pin "2") (pinfunction "2_2") (pintype "passive"))
      (node (ref "L5") (pin "1") (pinfunction "1_1") (pintype "passive"))
      (node (ref "U3") (pin "3") (pinfunction "INLO_3") (pintype "input"))
    )
    (net (code "37") (name "Net-(U3-VOUT)") (class "Default")
      (node (ref "R13") (pin "1") (pinfunction "1_1") (pintype "passive"))
      (node (ref "R2") (pin "1") (pinfunction "1_1") (pintype "passive"))
      (node (ref "R6") (pin "1") (pinfunction "1_1") (pintype "passive"))
      (node (ref "U3") (pin "8") (pinfunction "VOUT_8") (pintype "output"))
    )
    (net (code "38") (name "Net-(U3-VSET)") (class "Default")
      (node (ref "R13") (pin "2") (pinfunction "2_2") (pintype "passive"))
      (node (ref "U3") (pin "7") (pinfunction "VSET_7") (pintype "passive"))
    )
    (net (code "39") (name "Net-(U4-RFIN)") (class "Default")
      (node (ref "C9") (pin "2") (pinfunction "2_2") (pintype "passive"))
      (node (ref "U4") (pin "4") (pinfunction "RFIN_4") (pintype "input"))
    )
    (net (code "40") (name "Net-(U4-RFOUT{slash}BIAS)") (class "Default")
      (node (ref "C16") (pin "1") (pinfunction "1_1") (pintype "passive"))
      (node (ref "L4") (pin "1") (pinfunction "1_1") (pintype "passive"))
      (node (ref "U4") (pin "1") (pinfunction "RFOUT/BIAS_1") (pintype "output"))
    )
    (net (code "41") (name "Net-(U6-IN)") (class "Default")
      (node (ref "C33") (pin "1") (pinfunction "1_1") (pintype "passive"))
      (node (ref "L7") (pin "1") (pinfunction "1_1") (pintype "passive"))
      (node (ref "U6") (pin "1") (pinfunction "IN_1") (pintype "power_in"))
      (node (ref "U8") (pin "1") (pinfunction "IN_1") (pintype "power_in"))
      (node (ref "U8") (pin "3") (pinfunction "EN_3") (pintype "input"))
    )
    (net (code "42") (name "Net-(U7-AVCC)") (class "Default")
      (node (ref "C27") (pin "1") (pinfunction "1_1") (pintype "passive"))
      (node (ref "C31") (pin "1") (pinfunction "1_1") (pintype "passive"))
      (node (ref "L6") (pin "1") (pinfunction "1_1") (pintype "passive"))
      (node (ref "U7") (pin "39") (pinfunction "AVCC_39") (pintype "power_in"))
    )
    (net (code "43") (name "Net-(U7-PA4)") (class "Default")
      (node (ref "TP3") (pin "1") (pinfunction "1_1") (pintype "passive"))
      (node (ref "U7") (pin "44") (pinfunction "PA4_44") (pintype "bidirectional"))
    )
    (net (code "44") (name "Net-(U7-PA7)") (class "Default")
      (node (ref "TP2") (pin "1") (pinfunction "1_1") (pintype "passive"))
      (node (ref "U7") (pin "3") (pinfunction "PA7_3") (pintype "bidirectional"))
    )
    (net (code "45") (name "Net-(U7-PB3)") (class "Default")
      (node (ref "TP1") (pin "1") (pinfunction "1_1") (pintype "passive"))
      (node (ref "U7") (pin "7") (pinfunction "PB3_7") (pintype "bidirectional"))
    )
    (net (code "46") (name "Net-(U7-PD2)") (class "Default")
      (node (ref "TP4") (pin "1") (pinfunction "1_1") (pintype "passive"))
      (node (ref "U7") (pin "22") (pinfunction "PD2_22") (pintype "bidirectional"))
    )
    (net (code "47") (name "Net-(U7-PD3)") (class "Default")
      (node (ref "TP5") (pin "1") (pinfunction "1_1") (pintype "passive"))
      (node (ref "U7") (pin "23") (pinfunction "PD3_23") (pintype "bidirectional"))
    )
    (net (code "48") (name "Net-(U7-PD6)") (class "Default")
      (node (ref "D1") (pin "3") (pinfunction "CH1_3") (pintype "passive"))
      (node (ref "R22") (pin "1") (pinfunction "1_1") (pintype "passive"))
      (node (ref "U7") (pin "26") (pinfunction "PD6_26") (pintype "bidirectional"))
    )
    (net (code "49") (name "Net-(U7-PD7)") (class "Default")
      (node (ref "D1") (pin "2") (pinfunction "CH1_2") (pintype "passive"))
      (node (ref "R21") (pin "1") (pinfunction "1_1") (pintype "passive"))
      (node (ref "U7") (pin "27") (pinfunction "PD7_27") (pintype "bidirectional"))
    )
    (net (code "50") (name "Net-(U7-PR0)") (class "Default")
      (node (ref "C28") (pin "2") (pinfunction "2_2") (pintype "passive"))
      (node (ref "U7") (pin "36") (pinfunction "PR0_36") (pintype "passive"))
      (node (ref "Y1") (pin "1") (pinfunction "OSC1_1") (pintype "passive"))
    )
    (net (code "51") (name "Net-(U7-PR1)") (class "Default")
      (node (ref "C25") (pin "2") (pinfunction "2_2") (pintype "passive"))
      (node (ref "U7") (pin "37") (pinfunction "PR1_37") (pintype "passive"))
      (node (ref "Y1") (pin "3") (pinfunction "OSC2_3") (pintype "passive"))
    )
    (net (code "52") (name "Net-(X1-IN)") (class "Default")
      (node (ref "C4") (pin "2") (pinfunction "2_2") (pintype "passive"))
      (node (ref "X1") (pin "2") (pinfunction "IN_2") (pintype "input"))
    )
    (net (code "53") (name "Net-(X1-OUT)") (class "Default")
      (node (ref "C9") (pin "1") (pinfunction "1_1") (pintype "passive"))
      (node (ref "X1") (pin "5") (pinfunction "OUT_5") (pintype "output"))
    )
    (net (code "54") (name "Net-(X2-OUT1)") (class "Default")
      (node (ref "C20") (pin "1") (pinfunction "1_1") (pintype "passive"))
      (node (ref "X2") (pin "5") (pinfunction "OUT1_5") (pintype "output"))
    )
    (net (code "55") (name "Net-(X2-OUT2)") (class "Default")
      (node (ref "C19") (pin "1") (pinfunction "1_1") (pintype "passive"))
      (node (ref "X2") (pin "6") (pinfunction "OUT2_6") (pintype "output"))
    )
    (net (code "56") (name "Net-(X2-VIN1)") (class "Default")
      (node (ref "C18") (pin "2") (pinfunction "2_2") (pintype "passive"))
      (node (ref "X2") (pin "1") (pinfunction "VIN1_1") (pintype "input"))
    )
    (net (code "57") (name "Net-(X2-VIN2)") (class "Default")
      (node (ref "C16") (pin "2") (pinfunction "2_2") (pintype "passive"))
      (node (ref "X2") (pin "2") (pinfunction "VIN2_2") (pintype "input"))
    )
    (net (code "58") (name "VCC_FRONTEND") (class "Default")
      (node (ref "C23") (pin "1") (pinfunction "1_1") (pintype "passive"))
      (node (ref "L2") (pin "1") (pinfunction "1_1") (pintype "passive"))
      (node (ref "L3") (pin "1") (pinfunction "1_1") (pintype "passive"))
      (node (ref "R6") (pin "2") (pinfunction "2_2") (pintype "passive"))
      (node (ref "R7") (pin "1") (pinfunction "1_1") (pintype "passive"))
      (node (ref "U2") (pin "8") (pinfunction "V+_8") (pintype "power_in"))
      (node (ref "U6") (pin "5") (pinfunction "OUT_5") (pintype "power_in"))
    )
    (net (code "59") (name "unconnected-(J2-Pad3)") (class "Default")
      (node (ref "J2") (pin "3") (pinfunction "3_3") (pintype "passive+no_connect"))
    )
    (net (code "60") (name "unconnected-(J2-Pad4)") (class "Default")
      (node (ref "J2") (pin "4") (pinfunction "4_4") (pintype "passive+no_connect"))
    )
    (net (code "61") (name "unconnected-(U6-FB{slash}NC-Pad4)") (class "Default")
      (node (ref "U6") (pin "4") (pinfunction "FB/NC_4") (pintype "passive+no_connect"))
    )
    (net (code "62") (name "unconnected-(U7-PA2-Pad42)") (class "Default")
      (node (ref "U7") (pin "42") (pinfunction "PA2_42") (pintype "bidirectional+no_connect"))
    )
    (net (code "63") (name "unconnected-(U7-PA3-Pad43)") (class "Default")
      (node (ref "U7") (pin "43") (pinfunction "PA3_43") (pintype "bidirectional+no_connect"))
    )
    (net (code "64") (name "unconnected-(U7-PA5-Pad1)") (class "Default")
      (node (ref "U7") (pin "1") (pinfunction "PA5_1") (pintype "bidirectional"))
    )
    (net (code "65") (name "unconnected-(U7-PA6-Pad2)") (class "Default")
      (node (ref "U7") (pin "2") (pinfunction "PA6_2") (pintype "bidirectional+no_connect"))
    )
    (net (code "66") (name "unconnected-(U7-PC0-Pad10)") (class "Default")
      (node (ref "U7") (pin "10") (pinfunction "PC0_10") (pintype "bidirectional+no_connect"))
    )
    (net (code "67") (name "unconnected-(U7-PC1-Pad11)") (class "Default")
      (node (ref "U7") (pin "11") (pinfunction "PC1_11") (pintype "bidirectional+no_connect"))
    )
    (net (code "68") (name "unconnected-(U7-PC3-Pad13)") (class "Default")
      (node (ref "U7") (pin "13") (pinfunction "PC3_13") (pintype "bidirectional+no_connect"))
    )
    (net (code "69") (name "unconnected-(U7-PD0-Pad20)") (class "Default")
      (node (ref "U7") (pin "20") (pinfunction "PD0_20") (pintype "bidirectional+no_connect"))
    )
    (net (code "70") (name "unconnected-(U7-PD1-Pad21)") (class "Default")
      (node (ref "U7") (pin "21") (pinfunction "PD1_21") (pintype "bidirectional+no_connect"))
    )
    (net (code "71") (name "unconnected-(U7-PD4-Pad24)") (class "Default")
      (node (ref "U7") (pin "24") (pinfunction "PD4_24") (pintype "bidirectional+no_connect"))
    )
    (net (code "72") (name "unconnected-(U7-PD5-Pad25)") (class "Default")
      (node (ref "U7") (pin "25") (pinfunction "PD5_25") (pintype "bidirectional+no_connect"))
    )
    (net (code "73") (name "unconnected-(U7-PE0-Pad28)") (class "Default")
      (node (ref "U7") (pin "28") (pinfunction "PE0_28") (pintype "bidirectional+no_connect"))
    )
    (net (code "74") (name "unconnected-(U7-PE1-Pad29)") (class "Default")
      (node (ref "U7") (pin "29") (pinfunction "PE1_29") (pintype "bidirectional+no_connect"))
    )
    (net (code "75") (name "unconnected-(U7-PE2-Pad32)") (class "Default")
      (node (ref "U7") (pin "32") (pinfunction "PE2_32") (pintype "bidirectional+no_connect"))
    )
    (net (code "76") (name "unconnected-(U7-PE3-Pad33)") (class "Default")
      (node (ref "U7") (pin "33") (pinfunction "PE3_33") (pintype "bidirectional+no_connect"))
    )
    (net (code "77") (name "unconnected-(U8-FB{slash}NC-Pad4)") (class "Default")
      (node (ref "U8") (pin "4") (pinfunction "FB/NC_4") (pintype "passive+no_connect"))
    )
  )
)
